# ESP32S3.net
KiCad netlist of a schematic drawn in Altium Designer
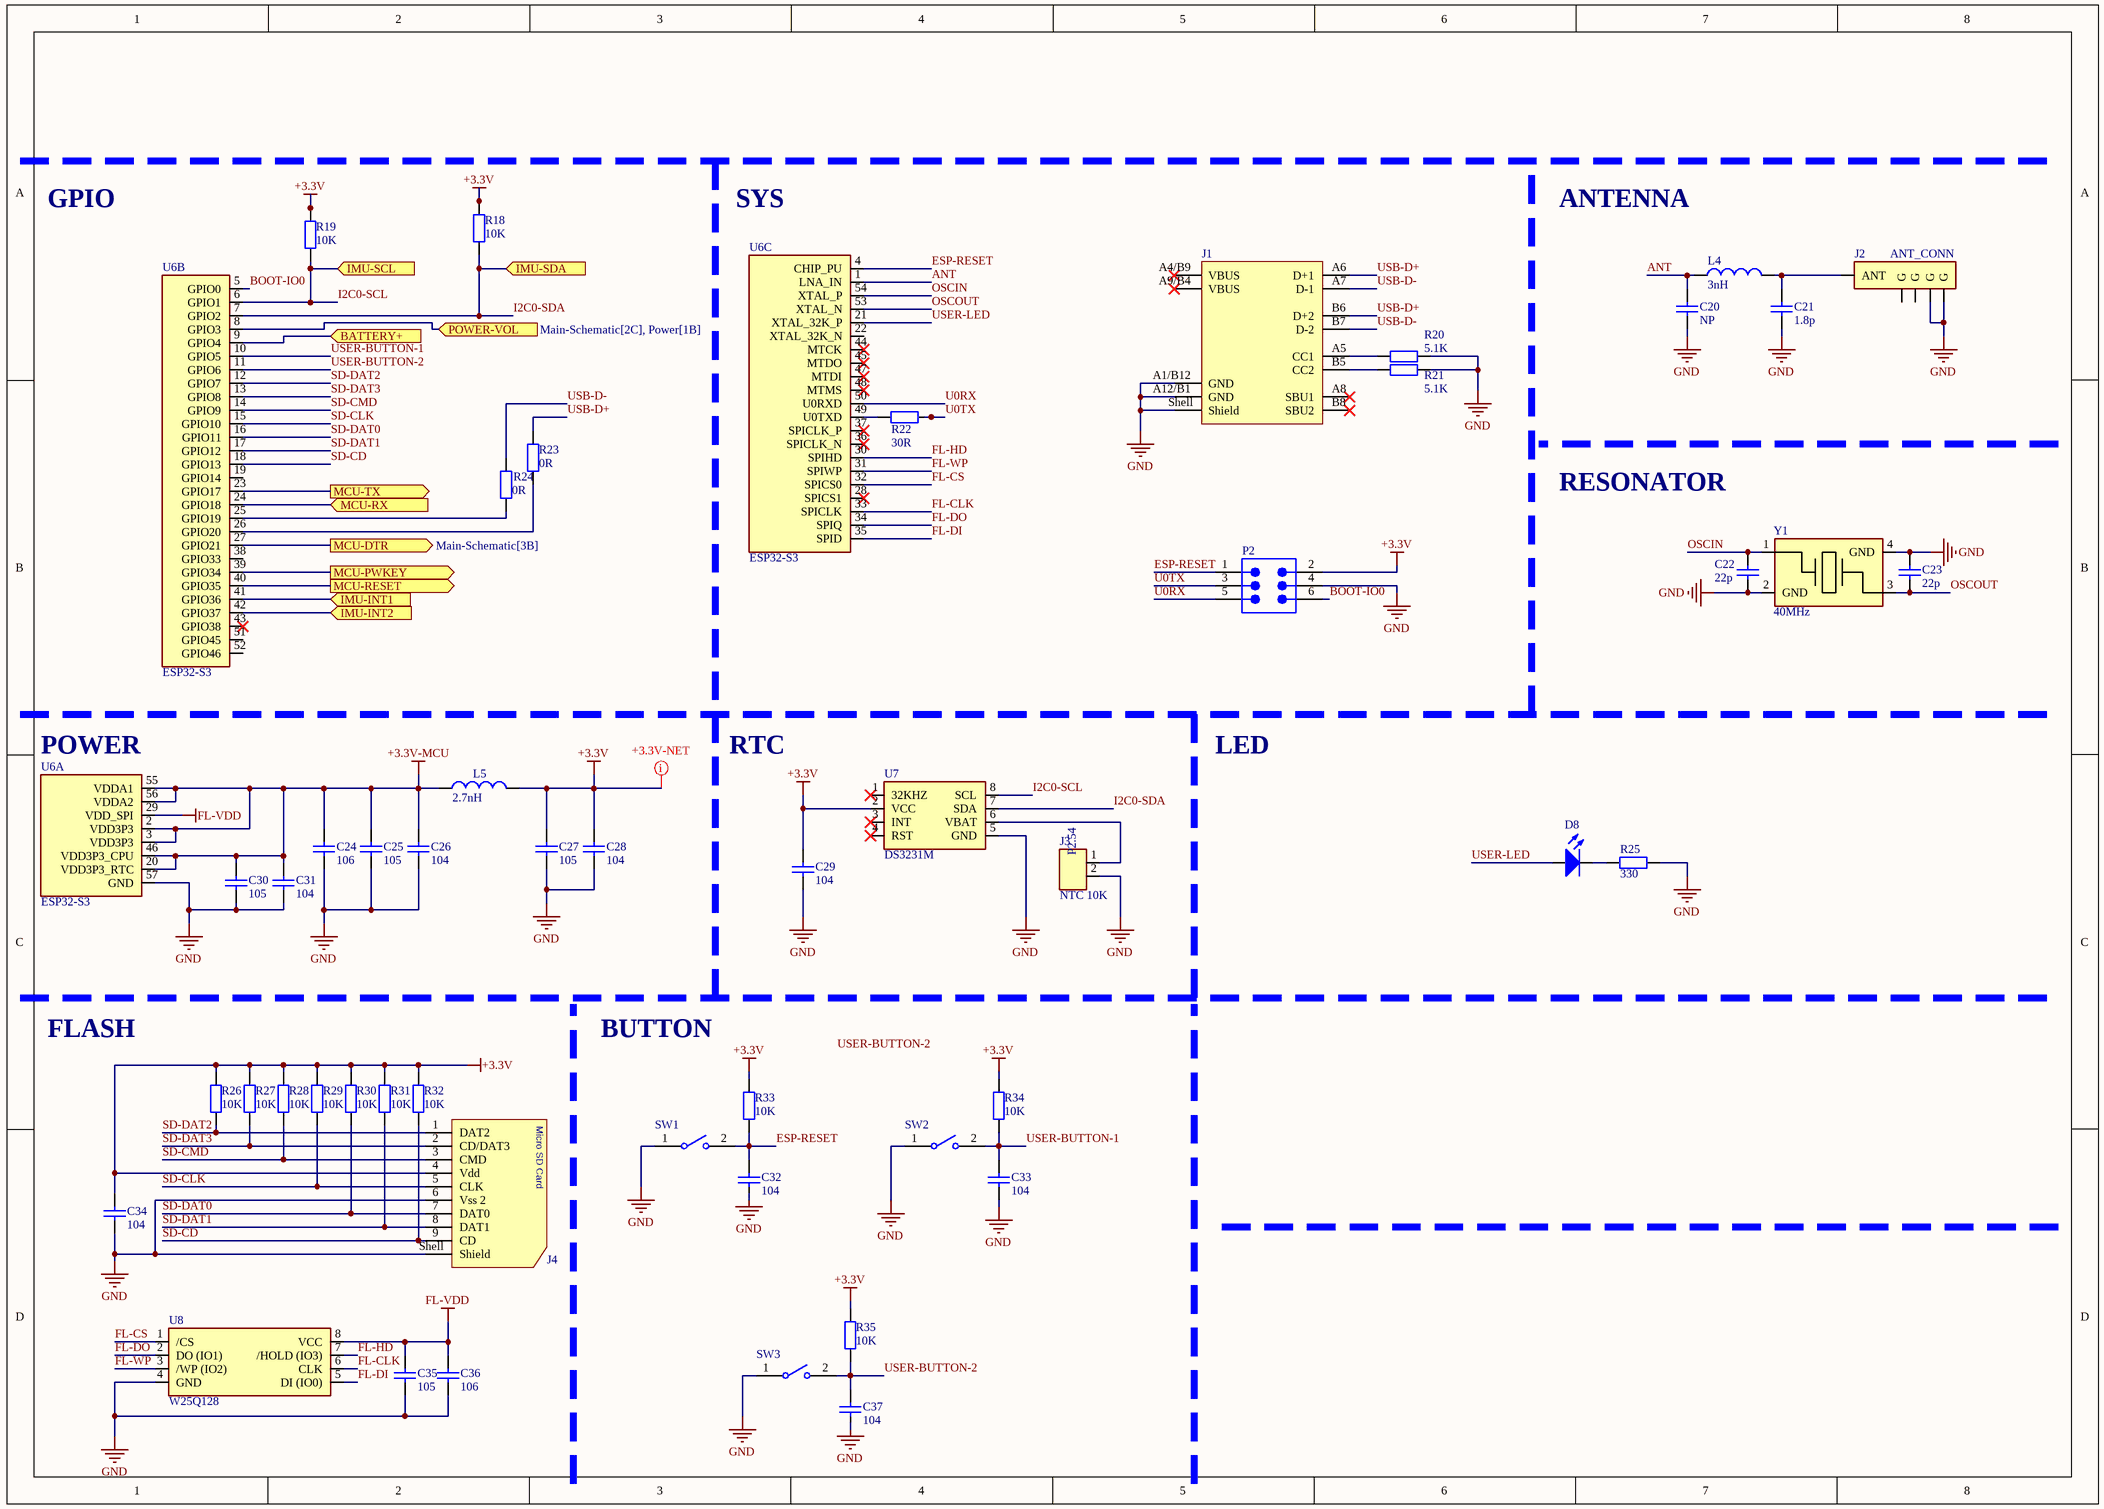
[diagram p0: ESP32S3.SchDoc]

(export (version "E")
  (design (tool "Eeschema 10.0.6"))
  (components
    (comp (ref "C20")
      (value "NP")
      (footprint "CAP_0603")
      (description "Non-polarized capacitor")
      (libsource (lib "Capacitor") (part "Cap_NP"))
    )
    (comp (ref "C21")
      (value "1.8p")
      (footprint "CAP_0603")
      (description "Non-polarized capacitor")
      (libsource (lib "Capacitor") (part "Cap_NP"))
    )
    (comp (ref "C22")
      (value "22p")
      (footprint "CAP_0603")
      (description "Non-polarized capacitor")
      (libsource (lib "Capacitor") (part "Cap_NP"))
    )
    (comp (ref "C23")
      (value "22p")
      (footprint "CAP_0603")
      (description "Non-polarized capacitor")
      (libsource (lib "Capacitor") (part "Cap_NP"))
    )
    (comp (ref "C24")
      (value "106")
      (footprint "CAP_0603")
      (description "Non-polarized capacitor")
      (libsource (lib "Capacitor") (part "Cap_NP"))
    )
    (comp (ref "C25")
      (value "105")
      (footprint "CAP_0603")
      (description "Non-polarized capacitor")
      (libsource (lib "Capacitor") (part "Cap_NP"))
    )
    (comp (ref "C26")
      (value "104")
      (footprint "CAP_0603")
      (description "Non-polarized capacitor")
      (libsource (lib "Capacitor") (part "Cap_NP"))
    )
    (comp (ref "C27")
      (value "105")
      (footprint "CAP_0603")
      (description "Non-polarized capacitor")
      (libsource (lib "Capacitor") (part "Cap_NP"))
    )
    (comp (ref "C28")
      (value "104")
      (footprint "CAP_0603")
      (description "Non-polarized capacitor")
      (libsource (lib "Capacitor") (part "Cap_NP"))
    )
    (comp (ref "C29")
      (value "104")
      (footprint "CAP_0603")
      (description "Non-polarized capacitor")
      (libsource (lib "Capacitor") (part "Cap_NP"))
    )
    (comp (ref "C30")
      (value "105")
      (footprint "CAP_0603")
      (description "Non-polarized capacitor")
      (libsource (lib "Capacitor") (part "Cap_NP"))
    )
    (comp (ref "C31")
      (value "104")
      (footprint "CAP_0603")
      (description "Non-polarized capacitor")
      (libsource (lib "Capacitor") (part "Cap_NP"))
    )
    (comp (ref "C32")
      (value "104")
      (footprint "CAP_0603")
      (description "Non-polarized capacitor")
      (libsource (lib "Capacitor") (part "Cap_NP"))
    )
    (comp (ref "C33")
      (value "104")
      (footprint "CAP_0603")
      (description "Non-polarized capacitor")
      (libsource (lib "Capacitor") (part "Cap_NP"))
    )
    (comp (ref "C34")
      (value "104")
      (footprint "CAP_0603")
      (description "Non-polarized capacitor")
      (libsource (lib "Capacitor") (part "Cap_NP"))
    )
    (comp (ref "C35")
      (value "105")
      (footprint "CAP_0603")
      (description "Non-polarized capacitor")
      (libsource (lib "Capacitor") (part "Cap_NP"))
    )
    (comp (ref "C36")
      (value "106")
      (footprint "CAP_0603")
      (description "Non-polarized capacitor")
      (libsource (lib "Capacitor") (part "Cap_NP"))
    )
    (comp (ref "C37")
      (value "104")
      (footprint "CAP_0603")
      (description "Non-polarized capacitor")
      (libsource (lib "Capacitor") (part "Cap_NP"))
    )
    (comp (ref "D8")
      (value "~")
      (footprint "LED-0805-Red")
      (description "Light Emitting Diode")
      (libsource (lib "Diode") (part "LED"))
    )
    (comp (ref "J1")
      (value "629722000214")
      (footprint "629722000214")
      (description "WR-COM USB 2.0 Type C Receptacle Horizontal SMT")
      (fields (field (name "MANUFACTURER") "Wurth Elektronik"))
      (libsource (lib "WE - Electromechanical Components") (part "USB 2.0_Type C_Receptacle_1 Port_629722000214"))
    )
    (comp (ref "J2")
      (value "ANT_CONN")
      (footprint "IPEX")
      (description "ATENNA PIN 1")
      (libsource (lib "Connector") (part "ANT_CONN"))
    )
    (comp (ref "J3")
      (value "NTC 10K")
      (footprint "XH2.54M-2")
      (libsource (lib "Connector") (part "Conn_Cai_2P_2.54"))
    )
    (comp (ref "J4")
      (value "693071040911")
      (footprint "693071040911")
      (description "WR-CRD SD Card Connector Push & Push Socket, 9 pins")
      (fields (field (name "MANUFACTURER") "Wurth Elektronik"))
      (libsource (lib "WE - Electromechanical Components") (part "Micro SD Card Socket_693071040911"))
    )
    (comp (ref "L4")
      (value "3nH")
      (footprint "INDC-0805")
      (description "Inductor")
      (fields (field (name "PUBLISHER") "Altium Limited"))
      (libsource (lib "Inductor") (part "Inductor"))
    )
    (comp (ref "L5")
      (value "2.7nH")
      (footprint "INDC-0805")
      (description "Inductor")
      (fields (field (name "PUBLISHER") "Altium Limited"))
      (libsource (lib "Inductor") (part "Inductor"))
    )
    (comp (ref "P2")
      (value "61200621621")
      (footprint "61200621621")
      (description "WR-BHD Male Box Header, THT Straight, pitch 2.54 mm, 2 Rows, 6 Pins")
      (fields (field (name "MANUFACTURER") "Wurth Elektronik"))
      (libsource (lib "WE - Electromechanical Components") (part "Header_Male_2R_06P"))
    )
    (comp (ref "R18") (value "10K") (footprint "RES_0603") (libsource (lib "") (part "Resistor_1")))
    (comp (ref "R19") (value "10K") (footprint "RES_0603") (libsource (lib "") (part "Resistor_1")))
    (comp (ref "R20") (value "5.1K") (footprint "RES_0603") (libsource (lib "Resistor") (part "Resistor")))
    (comp (ref "R21") (value "5.1K") (footprint "RES_0603") (libsource (lib "Resistor") (part "Resistor")))
    (comp (ref "R22") (value "30R") (footprint "RES_0603") (libsource (lib "Resistor") (part "Resistor")))
    (comp (ref "R23") (value "0R") (footprint "RES_0603") (libsource (lib "") (part "Resistor_1")))
    (comp (ref "R24") (value "0R") (footprint "RES_0603") (libsource (lib "") (part "Resistor_1")))
    (comp (ref "R25") (value "330") (footprint "RES_0603") (libsource (lib "Resistor") (part "Resistor")))
    (comp (ref "R26") (value "10K") (footprint "RES_0603") (libsource (lib "") (part "Resistor_1")))
    (comp (ref "R27") (value "10K") (footprint "RES_0603") (libsource (lib "") (part "Resistor_1")))
    (comp (ref "R28") (value "10K") (footprint "RES_0603") (libsource (lib "") (part "Resistor_1")))
    (comp (ref "R29") (value "10K") (footprint "RES_0603") (libsource (lib "") (part "Resistor_1")))
    (comp (ref "R30") (value "10K") (footprint "RES_0603") (libsource (lib "") (part "Resistor_1")))
    (comp (ref "R31") (value "10K") (footprint "RES_0603") (libsource (lib "") (part "Resistor_1")))
    (comp (ref "R32") (value "10K") (footprint "RES_0603") (libsource (lib "") (part "Resistor_1")))
    (comp (ref "R33") (value "10K") (footprint "RES_0603") (libsource (lib "") (part "Resistor_1")))
    (comp (ref "R34") (value "10K") (footprint "RES_0603") (libsource (lib "") (part "Resistor_1")))
    (comp (ref "R35") (value "10K") (footprint "RES_0603") (libsource (lib "") (part "Resistor_1")))
    (comp (ref "SW1")
      (value "434121050816")
      (footprint "434121050816")
      (description "WS-TASV SMT Tact Switch, 6mm x 3.5mm, 160gf, SPST-NO, 12V, 50mA")
      (fields (field (name "MANUFACTURER") "Wurth Elektronik"))
      (libsource (lib "WE - Electromechanical Components") (part "SPST-NO_2P"))
    )
    (comp (ref "SW2")
      (value "434121050816")
      (footprint "434121050816")
      (description "WS-TASV SMT Tact Switch, 6mm x 3.5mm, 160gf, SPST-NO, 12V, 50mA")
      (fields (field (name "MANUFACTURER") "Wurth Elektronik"))
      (libsource (lib "WE - Electromechanical Components") (part "SPST-NO_2P"))
    )
    (comp (ref "SW3")
      (value "434121050816")
      (footprint "434121050816")
      (description "WS-TASV SMT Tact Switch, 6mm x 3.5mm, 160gf, SPST-NO, 12V, 50mA")
      (fields (field (name "MANUFACTURER") "Wurth Elektronik"))
      (libsource (lib "WE - Electromechanical Components") (part "SPST-NO_2P"))
    )
    (comp (ref "U6") (value "ESP32-S3") (footprint "QFN56") (libsource (lib "IC") (part "ESP32-S3")))
    (comp (ref "U7")
      (value "DS3231M")
      (footprint "SOP8-P1.27")
      (description "I2C realtime clock (RTC)")
      (libsource (lib "IC") (part "DS3231M"))
    )
    (comp (ref "U8")
      (value "W25Q128")
      (footprint "SOIC127P790X216-8N")
      (description "256M-bit (32MB) Serial Flash memory")
      (libsource (lib "IC") (part "W25Q256JV"))
    )
    (comp (ref "Y1") (value "40MHz") (footprint "Y-3225") (libsource (lib "IC") (part "Resonator")))
  )
  (nets
    (net (code "1") (name "+3.3V") (class "Default")
      (node (ref "C27") (pin "2") (pinfunction "2_2") (pintype "passive"))
      (node (ref "C28") (pin "2") (pinfunction "2_2") (pintype "passive"))
      (node (ref "C29") (pin "1") (pinfunction "1_1") (pintype "passive"))
      (node (ref "C34") (pin "2") (pinfunction "2_2") (pintype "passive"))
      (node (ref "J4") (pin "4") (pinfunction "Vdd_4") (pintype "passive"))
      (node (ref "L5") (pin "2") (pinfunction "2_2") (pintype "passive"))
      (node (ref "P2") (pin "2") (pinfunction "2_2") (pintype "passive"))
      (node (ref "R18") (pin "2") (pinfunction "2_2") (pintype "passive"))
      (node (ref "R19") (pin "2") (pinfunction "2_2") (pintype "passive"))
      (node (ref "R26") (pin "2") (pinfunction "2_2") (pintype "passive"))
      (node (ref "R27") (pin "2") (pinfunction "2_2") (pintype "passive"))
      (node (ref "R28") (pin "2") (pinfunction "2_2") (pintype "passive"))
      (node (ref "R29") (pin "2") (pinfunction "2_2") (pintype "passive"))
      (node (ref "R30") (pin "2") (pinfunction "2_2") (pintype "passive"))
      (node (ref "R31") (pin "2") (pinfunction "2_2") (pintype "passive"))
      (node (ref "R32") (pin "2") (pinfunction "2_2") (pintype "passive"))
      (node (ref "R33") (pin "2") (pinfunction "2_2") (pintype "passive"))
      (node (ref "R34") (pin "2") (pinfunction "2_2") (pintype "passive"))
      (node (ref "R35") (pin "2") (pinfunction "2_2") (pintype "passive"))
      (node (ref "U7") (pin "2") (pinfunction "VCC_2") (pintype "passive"))
    )
    (net (code "2") (name "+3.3V-MCU") (class "Default")
      (node (ref "C24") (pin "2") (pinfunction "2_2") (pintype "passive"))
      (node (ref "C25") (pin "2") (pinfunction "2_2") (pintype "passive"))
      (node (ref "C26") (pin "2") (pinfunction "2_2") (pintype "passive"))
      (node (ref "C30") (pin "2") (pinfunction "2_2") (pintype "passive"))
      (node (ref "C31") (pin "2") (pinfunction "2_2") (pintype "passive"))
      (node (ref "L5") (pin "1") (pinfunction "1_1") (pintype "passive"))
      (node (ref "U6") (pin "2") (pinfunction "VDD3P3_2") (pintype "passive"))
      (node (ref "U6") (pin "20") (pinfunction "VDD3P3_RTC_20") (pintype "passive"))
      (node (ref "U6") (pin "3") (pinfunction "VDD3P3_3") (pintype "passive"))
      (node (ref "U6") (pin "46") (pinfunction "VDD3P3_CPU_46") (pintype "passive"))
      (node (ref "U6") (pin "55") (pinfunction "VDDA1_55") (pintype "passive"))
      (node (ref "U6") (pin "56") (pinfunction "VDDA2_56") (pintype "passive"))
    )
    (net (code "3") (name "/ANT") (class "Default")
      (node (ref "C20") (pin "2") (pinfunction "2_2") (pintype "passive"))
      (node (ref "L4") (pin "1") (pinfunction "1_1") (pintype "passive"))
      (node (ref "U6") (pin "1") (pinfunction "LNA_IN_1") (pintype "passive"))
    )
    (net (code "4") (name "/BATTERY+") (class "Default")
      (node (ref "U6") (pin "9") (pinfunction "GPIO4_9") (pintype "passive"))
    )
    (net (code "5") (name "/BOOT-IO0") (class "Default")
      (node (ref "P2") (pin "6") (pinfunction "6_6") (pintype "passive"))
      (node (ref "U6") (pin "5") (pinfunction "GPIO0_5") (pintype "passive"))
    )
    (net (code "6") (name "/ESP-RESET") (class "Default")
      (node (ref "C32") (pin "1") (pinfunction "1_1") (pintype "passive"))
      (node (ref "P2") (pin "1") (pinfunction "1_1") (pintype "passive"))
      (node (ref "R33") (pin "1") (pinfunction "1_1") (pintype "passive"))
      (node (ref "SW1") (pin "2") (pinfunction "2_2") (pintype "passive"))
      (node (ref "U6") (pin "4") (pinfunction "CHIP_PU_4") (pintype "passive"))
    )
    (net (code "7") (name "/FL-CLK") (class "Default")
      (node (ref "U6") (pin "33") (pinfunction "SPICLK_33") (pintype "passive"))
      (node (ref "U8") (pin "6") (pinfunction "CLK_6") (pintype "passive"))
    )
    (net (code "8") (name "/FL-CS") (class "Default")
      (node (ref "U6") (pin "32") (pinfunction "SPICS0_32") (pintype "passive"))
      (node (ref "U8") (pin "1") (pinfunction "/CS_1") (pintype "passive"))
    )
    (net (code "9") (name "/FL-DI") (class "Default")
      (node (ref "U6") (pin "35") (pinfunction "SPID_35") (pintype "passive"))
      (node (ref "U8") (pin "5") (pinfunction "DI_(IO0)_5") (pintype "passive"))
    )
    (net (code "10") (name "/FL-DO") (class "Default")
      (node (ref "U6") (pin "34") (pinfunction "SPIQ_34") (pintype "passive"))
      (node (ref "U8") (pin "2") (pinfunction "DO_(IO1)_2") (pintype "passive"))
    )
    (net (code "11") (name "/FL-HD") (class "Default")
      (node (ref "U6") (pin "30") (pinfunction "SPIHD_30") (pintype "passive"))
      (node (ref "U8") (pin "7") (pinfunction "/HOLD_(IO3)_7") (pintype "passive"))
    )
    (net (code "12") (name "/FL-WP") (class "Default")
      (node (ref "U6") (pin "31") (pinfunction "SPIWP_31") (pintype "passive"))
      (node (ref "U8") (pin "3") (pinfunction "/WP_(IO2)_3") (pintype "passive"))
    )
    (net (code "13") (name "/I2C0-SCL") (class "Default")
      (node (ref "R19") (pin "1") (pinfunction "1_1") (pintype "passive"))
      (node (ref "U6") (pin "6") (pinfunction "GPIO1_6") (pintype "passive"))
      (node (ref "U7") (pin "8") (pinfunction "SCL_8") (pintype "passive"))
    )
    (net (code "14") (name "/I2C0-SDA") (class "Default")
      (node (ref "R18") (pin "1") (pinfunction "1_1") (pintype "passive"))
      (node (ref "U6") (pin "7") (pinfunction "GPIO2_7") (pintype "passive"))
      (node (ref "U7") (pin "7") (pinfunction "SDA_7") (pintype "passive"))
    )
    (net (code "15") (name "/IMU-INT1") (class "Default")
      (node (ref "U6") (pin "41") (pinfunction "GPIO36_41") (pintype "passive"))
    )
    (net (code "16") (name "/IMU-INT2") (class "Default")
      (node (ref "U6") (pin "42") (pinfunction "GPIO37_42") (pintype "passive"))
    )
    (net (code "17") (name "/MCU-DTR") (class "Default")
      (node (ref "U6") (pin "27") (pinfunction "GPIO21_27") (pintype "passive"))
    )
    (net (code "18") (name "/MCU-PWKEY") (class "Default")
      (node (ref "U6") (pin "39") (pinfunction "GPIO34_39") (pintype "passive"))
    )
    (net (code "19") (name "/MCU-RESET") (class "Default")
      (node (ref "U6") (pin "40") (pinfunction "GPIO35_40") (pintype "passive"))
    )
    (net (code "20") (name "/MCU-RX") (class "Default")
      (node (ref "U6") (pin "24") (pinfunction "GPIO18_24") (pintype "passive"))
    )
    (net (code "21") (name "/MCU-TX") (class "Default")
      (node (ref "U6") (pin "23") (pinfunction "GPIO17_23") (pintype "passive"))
    )
    (net (code "22") (name "/OSCIN") (class "Default")
      (node (ref "C22") (pin "2") (pinfunction "2_2") (pintype "passive"))
      (node (ref "U6") (pin "54") (pinfunction "XTAL_P_54") (pintype "passive"))
      (node (ref "Y1") (pin "1") (pinfunction "OSCIN_1") (pintype "passive"))
    )
    (net (code "23") (name "/OSCOUT") (class "Default")
      (node (ref "C23") (pin "1") (pinfunction "1_1") (pintype "passive"))
      (node (ref "U6") (pin "53") (pinfunction "XTAL_N_53") (pintype "passive"))
      (node (ref "Y1") (pin "3") (pinfunction "OSCOUT_3") (pintype "passive"))
    )
    (net (code "24") (name "/POWER-VOL") (class "Default")
      (node (ref "U6") (pin "8") (pinfunction "GPIO3_8") (pintype "passive"))
    )
    (net (code "25") (name "/SD-CD") (class "Default")
      (node (ref "J4") (pin "9") (pinfunction "CD_9") (pintype "passive"))
      (node (ref "R32") (pin "1") (pinfunction "1_1") (pintype "passive"))
      (node (ref "U6") (pin "18") (pinfunction "GPIO13_18") (pintype "passive"))
    )
    (net (code "26") (name "/SD-CLK") (class "Default")
      (node (ref "J4") (pin "5") (pinfunction "CLK_5") (pintype "passive"))
      (node (ref "R29") (pin "1") (pinfunction "1_1") (pintype "passive"))
      (node (ref "U6") (pin "15") (pinfunction "GPIO10_15") (pintype "passive"))
    )
    (net (code "27") (name "/SD-CMD") (class "Default")
      (node (ref "J4") (pin "3") (pinfunction "CMD_3") (pintype "passive"))
      (node (ref "R28") (pin "1") (pinfunction "1_1") (pintype "passive"))
      (node (ref "U6") (pin "14") (pinfunction "GPIO9_14") (pintype "passive"))
    )
    (net (code "28") (name "/SD-DAT0") (class "Default")
      (node (ref "J4") (pin "7") (pinfunction "DAT0_7") (pintype "passive"))
      (node (ref "R30") (pin "1") (pinfunction "1_1") (pintype "passive"))
      (node (ref "U6") (pin "16") (pinfunction "GPIO11_16") (pintype "passive"))
    )
    (net (code "29") (name "/SD-DAT1") (class "Default")
      (node (ref "J4") (pin "8") (pinfunction "DAT1_8") (pintype "passive"))
      (node (ref "R31") (pin "1") (pinfunction "1_1") (pintype "passive"))
      (node (ref "U6") (pin "17") (pinfunction "GPIO12_17") (pintype "passive"))
    )
    (net (code "30") (name "/SD-DAT2") (class "Default")
      (node (ref "J4") (pin "1") (pinfunction "DAT2_1") (pintype "passive"))
      (node (ref "R26") (pin "1") (pinfunction "1_1") (pintype "passive"))
      (node (ref "U6") (pin "12") (pinfunction "GPIO7_12") (pintype "passive"))
    )
    (net (code "31") (name "/SD-DAT3") (class "Default")
      (node (ref "J4") (pin "2") (pinfunction "CD/DAT3_2") (pintype "passive"))
      (node (ref "R27") (pin "1") (pinfunction "1_1") (pintype "passive"))
      (node (ref "U6") (pin "13") (pinfunction "GPIO8_13") (pintype "passive"))
    )
    (net (code "32") (name "/U0RX") (class "Default")
      (node (ref "P2") (pin "5") (pinfunction "5_5") (pintype "passive"))
      (node (ref "U6") (pin "50") (pinfunction "U0RXD_50") (pintype "passive"))
    )
    (net (code "33") (name "/U0TX") (class "Default")
      (node (ref "P2") (pin "3") (pinfunction "3_3") (pintype "passive"))
      (node (ref "R22") (pin "2") (pinfunction "2_2") (pintype "passive"))
    )
    (net (code "34") (name "/USB-D+") (class "Default")
      (node (ref "J1") (pin "A6") (pinfunction "D+1_A6") (pintype "passive"))
      (node (ref "J1") (pin "B6") (pinfunction "D+2_B6") (pintype "passive"))
      (node (ref "R23") (pin "2") (pinfunction "2_2") (pintype "passive"))
    )
    (net (code "35") (name "/USB-D-") (class "Default")
      (node (ref "J1") (pin "A7") (pinfunction "D-1_A7") (pintype "passive"))
      (node (ref "J1") (pin "B7") (pinfunction "D-2_B7") (pintype "passive"))
      (node (ref "R24") (pin "2") (pinfunction "2_2") (pintype "passive"))
    )
    (net (code "36") (name "/USER-BUTTON-1") (class "Default")
      (node (ref "C33") (pin "1") (pinfunction "1_1") (pintype "passive"))
      (node (ref "R34") (pin "1") (pinfunction "1_1") (pintype "passive"))
      (node (ref "SW2") (pin "2") (pinfunction "2_2") (pintype "passive"))
      (node (ref "U6") (pin "10") (pinfunction "GPIO5_10") (pintype "passive"))
    )
    (net (code "37") (name "/USER-BUTTON-2") (class "Default")
      (node (ref "C37") (pin "1") (pinfunction "1_1") (pintype "passive"))
      (node (ref "R35") (pin "1") (pinfunction "1_1") (pintype "passive"))
      (node (ref "SW3") (pin "2") (pinfunction "2_2") (pintype "passive"))
      (node (ref "U6") (pin "11") (pinfunction "GPIO6_11") (pintype "passive"))
    )
    (net (code "38") (name "/USER-LED") (class "Default")
      (node (ref "D8") (pin "1") (pinfunction "A_1") (pintype "passive"))
      (node (ref "U6") (pin "21") (pinfunction "XTAL_32K_P_21") (pintype "passive"))
    )
    (net (code "39") (name "FL-VDD") (class "Default")
      (node (ref "C35") (pin "2") (pinfunction "2_2") (pintype "passive"))
      (node (ref "C36") (pin "2") (pinfunction "2_2") (pintype "passive"))
      (node (ref "U6") (pin "29") (pinfunction "VDD_SPI_29") (pintype "passive"))
      (node (ref "U8") (pin "8") (pinfunction "VCC_8") (pintype "passive"))
    )
    (net (code "40") (name "GND") (class "Default")
      (node (ref "C20") (pin "1") (pinfunction "1_1") (pintype "passive"))
      (node (ref "C21") (pin "1") (pinfunction "1_1") (pintype "passive"))
      (node (ref "C22") (pin "1") (pinfunction "1_1") (pintype "passive"))
      (node (ref "C23") (pin "2") (pinfunction "2_2") (pintype "passive"))
      (node (ref "C24") (pin "1") (pinfunction "1_1") (pintype "passive"))
      (node (ref "C25") (pin "1") (pinfunction "1_1") (pintype "passive"))
      (node (ref "C26") (pin "1") (pinfunction "1_1") (pintype "passive"))
      (node (ref "C27") (pin "1") (pinfunction "1_1") (pintype "passive"))
      (node (ref "C28") (pin "1") (pinfunction "1_1") (pintype "passive"))
      (node (ref "C29") (pin "2") (pinfunction "2_2") (pintype "passive"))
      (node (ref "C30") (pin "1") (pinfunction "1_1") (pintype "passive"))
      (node (ref "C31") (pin "1") (pinfunction "1_1") (pintype "passive"))
      (node (ref "C32") (pin "2") (pinfunction "2_2") (pintype "passive"))
      (node (ref "C33") (pin "2") (pinfunction "2_2") (pintype "passive"))
      (node (ref "C34") (pin "1") (pinfunction "1_1") (pintype "passive"))
      (node (ref "C35") (pin "1") (pinfunction "1_1") (pintype "passive"))
      (node (ref "C36") (pin "1") (pinfunction "1_1") (pintype "passive"))
      (node (ref "C37") (pin "2") (pinfunction "2_2") (pintype "passive"))
      (node (ref "J1") (pin "A1/B12") (pinfunction "GND_A1/B12") (pintype "passive"))
      (node (ref "J1") (pin "A12/B1") (pinfunction "GND_A12/B1") (pintype "passive"))
      (node (ref "J1") (pin "Shell") (pinfunction "Shield_Shell") (pintype "passive"))
      (node (ref "J2") (pin "4") (pinfunction "G_4") (pintype "passive"))
      (node (ref "J2") (pin "5") (pinfunction "G_5") (pintype "passive"))
      (node (ref "J3") (pin "2") (pintype "passive"))
      (node (ref "J4") (pin "6") (pinfunction "Vss_2_6") (pintype "passive"))
      (node (ref "J4") (pin "Shell") (pinfunction "Shield_Shell") (pintype "passive"))
      (node (ref "P2") (pin "4") (pinfunction "4_4") (pintype "passive"))
      (node (ref "R20") (pin "2") (pinfunction "2_2") (pintype "passive"))
      (node (ref "R21") (pin "2") (pinfunction "2_2") (pintype "passive"))
      (node (ref "R25") (pin "2") (pinfunction "2_2") (pintype "passive"))
      (node (ref "SW1") (pin "1") (pinfunction "1_1") (pintype "passive"))
      (node (ref "SW2") (pin "1") (pinfunction "1_1") (pintype "passive"))
      (node (ref "SW3") (pin "1") (pinfunction "1_1") (pintype "passive"))
      (node (ref "U6") (pin "57") (pinfunction "GND_57") (pintype "passive"))
      (node (ref "U7") (pin "5") (pinfunction "GND_5") (pintype "passive"))
      (node (ref "U8") (pin "4") (pinfunction "GND_4") (pintype "passive"))
      (node (ref "Y1") (pin "2") (pinfunction "GND_2") (pintype "passive"))
      (node (ref "Y1") (pin "4") (pinfunction "GND_4") (pintype "passive"))
    )
    (net (code "41") (name "Net-(D8-K)") (class "Default")
      (node (ref "D8") (pin "2") (pinfunction "K_2") (pintype "passive"))
      (node (ref "R25") (pin "1") (pinfunction "1_1") (pintype "passive"))
    )
    (net (code "42") (name "Net-(J1-CC1)") (class "Default")
      (node (ref "J1") (pin "A5") (pinfunction "CC1_A5") (pintype "passive"))
      (node (ref "R20") (pin "1") (pinfunction "1_1") (pintype "passive"))
    )
    (net (code "43") (name "Net-(J1-CC2)") (class "Default")
      (node (ref "J1") (pin "B5") (pinfunction "CC2_B5") (pintype "passive"))
      (node (ref "R21") (pin "1") (pinfunction "1_1") (pintype "passive"))
    )
    (net (code "44") (name "Net-(J2-ANT)") (class "Default")
      (node (ref "C21") (pin "2") (pinfunction "2_2") (pintype "passive"))
      (node (ref "J2") (pin "1") (pinfunction "ANT_1") (pintype "passive"))
      (node (ref "L4") (pin "2") (pinfunction "2_2") (pintype "passive"))
    )
    (net (code "45") (name "Net-(U6B-GPIO19)") (class "Default")
      (node (ref "R24") (pin "1") (pinfunction "1_1") (pintype "passive"))
      (node (ref "U6") (pin "25") (pinfunction "GPIO19_25") (pintype "passive"))
    )
    (net (code "46") (name "Net-(U6B-GPIO20)") (class "Default")
      (node (ref "R23") (pin "1") (pinfunction "1_1") (pintype "passive"))
      (node (ref "U6") (pin "26") (pinfunction "GPIO20_26") (pintype "passive"))
    )
    (net (code "47") (name "Net-(U6C-U0TXD)") (class "Default")
      (node (ref "R22") (pin "1") (pinfunction "1_1") (pintype "passive"))
      (node (ref "U6") (pin "49") (pinfunction "U0TXD_49") (pintype "passive"))
    )
    (net (code "48") (name "Net-(U7-VBAT)") (class "Default")
      (node (ref "J3") (pin "1") (pintype "passive"))
      (node (ref "U7") (pin "6") (pinfunction "VBAT_6") (pintype "passive"))
    )
    (net (code "49") (name "unconnected-(J1-SBU1-PadA8)") (class "Default")
      (node (ref "J1") (pin "A8") (pinfunction "SBU1_A8") (pintype "passive+no_connect"))
    )
    (net (code "50") (name "unconnected-(J1-SBU2-PadB8)") (class "Default")
      (node (ref "J1") (pin "B8") (pinfunction "SBU2_B8") (pintype "passive+no_connect"))
    )
    (net (code "51") (name "unconnected-(J1-VBUS-PadA4{slash}B9)") (class "Default")
      (node (ref "J1") (pin "A4/B9") (pinfunction "VBUS_A4/B9") (pintype "passive+no_connect"))
    )
    (net (code "52") (name "unconnected-(J1-VBUS-PadA9{slash}B4)") (class "Default")
      (node (ref "J1") (pin "A9/B4") (pinfunction "VBUS_A9/B4") (pintype "passive+no_connect"))
    )
    (net (code "53") (name "unconnected-(J2-G-Pad2)") (class "Default")
      (node (ref "J2") (pin "2") (pinfunction "G_2") (pintype "passive"))
    )
    (net (code "54") (name "unconnected-(J2-G-Pad3)") (class "Default")
      (node (ref "J2") (pin "3") (pinfunction "G_3") (pintype "passive"))
    )
    (net (code "55") (name "unconnected-(U6B-GPIO14-Pad19)") (class "Default")
      (node (ref "U6") (pin "19") (pinfunction "GPIO14_19") (pintype "passive"))
    )
    (net (code "56") (name "unconnected-(U6B-GPIO33-Pad38)") (class "Default")
      (node (ref "U6") (pin "38") (pinfunction "GPIO33_38") (pintype "passive"))
    )
    (net (code "57") (name "unconnected-(U6B-GPIO38-Pad43)") (class "Default")
      (node (ref "U6") (pin "43") (pinfunction "GPIO38_43") (pintype "passive+no_connect"))
    )
    (net (code "58") (name "unconnected-(U6B-GPIO45-Pad51)") (class "Default")
      (node (ref "U6") (pin "51") (pinfunction "GPIO45_51") (pintype "passive"))
    )
    (net (code "59") (name "unconnected-(U6B-GPIO46-Pad52)") (class "Default")
      (node (ref "U6") (pin "52") (pinfunction "GPIO46_52") (pintype "passive"))
    )
    (net (code "60") (name "unconnected-(U6C-MTCK-Pad44)") (class "Default")
      (node (ref "U6") (pin "44") (pinfunction "MTCK_44") (pintype "passive+no_connect"))
    )
    (net (code "61") (name "unconnected-(U6C-MTDI-Pad47)") (class "Default")
      (node (ref "U6") (pin "47") (pinfunction "MTDI_47") (pintype "passive+no_connect"))
    )
    (net (code "62") (name "unconnected-(U6C-MTDO-Pad45)") (class "Default")
      (node (ref "U6") (pin "45") (pinfunction "MTDO_45") (pintype "passive+no_connect"))
    )
    (net (code "63") (name "unconnected-(U6C-MTMS-Pad48)") (class "Default")
      (node (ref "U6") (pin "48") (pinfunction "MTMS_48") (pintype "passive+no_connect"))
    )
    (net (code "64") (name "unconnected-(U6C-SPICLK_N-Pad36)") (class "Default")
      (node (ref "U6") (pin "36") (pinfunction "SPICLK_N_36") (pintype "passive+no_connect"))
    )
    (net (code "65") (name "unconnected-(U6C-SPICLK_P-Pad37)") (class "Default")
      (node (ref "U6") (pin "37") (pinfunction "SPICLK_P_37") (pintype "passive+no_connect"))
    )
    (net (code "66") (name "unconnected-(U6C-SPICS1-Pad28)") (class "Default")
      (node (ref "U6") (pin "28") (pinfunction "SPICS1_28") (pintype "passive+no_connect"))
    )
    (net (code "67") (name "unconnected-(U6C-XTAL_32K_N-Pad22)") (class "Default")
      (node (ref "U6") (pin "22") (pinfunction "XTAL_32K_N_22") (pintype "passive"))
    )
    (net (code "68") (name "unconnected-(U7-32KHZ-Pad1)") (class "Default")
      (node (ref "U7") (pin "1") (pinfunction "32KHZ_1") (pintype "passive+no_connect"))
    )
    (net (code "69") (name "unconnected-(U7-INT-Pad3)") (class "Default")
      (node (ref "U7") (pin "3") (pinfunction "INT_3") (pintype "passive+no_connect"))
    )
    (net (code "70") (name "unconnected-(U7-RST-Pad4)") (class "Default")
      (node (ref "U7") (pin "4") (pinfunction "RST_4") (pintype "passive+no_connect"))
    )
  )
)
